# Buttons.net
KiCad netlist of a schematic drawn in Altium Designer
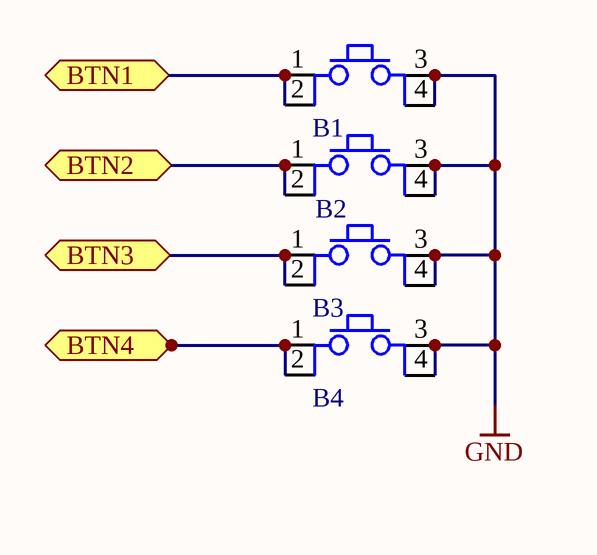
[diagram p0: Buttons.SchDoc]

(export (version "E")
  (design (tool "Eeschema 10.0.6"))
  (components
    (comp (ref "B1")
      (value "Button")
      (footprint "FP_BTN_SMD")
      (description "Push button")
      (libsource (lib "hallglib") (part "Button 4P"))
    )
    (comp (ref "B2")
      (value "Button")
      (footprint "FP_BTN_SMD")
      (description "Push button")
      (libsource (lib "hallglib") (part "Button 4P"))
    )
    (comp (ref "B3")
      (value "Button")
      (footprint "FP_BTN_SMD")
      (description "Push button")
      (libsource (lib "hallglib") (part "Button 4P"))
    )
    (comp (ref "B4")
      (value "Button")
      (footprint "FP_BTN_SMD")
      (description "Push button")
      (libsource (lib "hallglib") (part "Button 4P"))
    )
  )
  (nets
    (net (code "1") (name "/BTN1") (class "Default")
      (node (ref "B1") (pin "1") (pinfunction "1_1") (pintype "passive"))
      (node (ref "B1") (pin "2") (pinfunction "2_2") (pintype "passive"))
    )
    (net (code "2") (name "/BTN2") (class "Default")
      (node (ref "B2") (pin "1") (pinfunction "1_1") (pintype "passive"))
      (node (ref "B2") (pin "2") (pinfunction "2_2") (pintype "passive"))
    )
    (net (code "3") (name "/BTN3") (class "Default")
      (node (ref "B3") (pin "1") (pinfunction "1_1") (pintype "passive"))
      (node (ref "B3") (pin "2") (pinfunction "2_2") (pintype "passive"))
    )
    (net (code "4") (name "/BTN4") (class "Default")
      (node (ref "B4") (pin "1") (pinfunction "1_1") (pintype "passive"))
      (node (ref "B4") (pin "2") (pinfunction "2_2") (pintype "passive"))
    )
    (net (code "5") (name "GND") (class "Default")
      (node (ref "B1") (pin "3") (pinfunction "3_3") (pintype "passive"))
      (node (ref "B1") (pin "4") (pinfunction "4_4") (pintype "passive"))
      (node (ref "B2") (pin "3") (pinfunction "3_3") (pintype "passive"))
      (node (ref "B2") (pin "4") (pinfunction "4_4") (pintype "passive"))
      (node (ref "B3") (pin "3") (pinfunction "3_3") (pintype "passive"))
      (node (ref "B3") (pin "4") (pinfunction "4_4") (pintype "passive"))
      (node (ref "B4") (pin "3") (pinfunction "3_3") (pintype "passive"))
      (node (ref "B4") (pin "4") (pinfunction "4_4") (pintype "passive"))
    )
  )
)
